# Power.net
KiCad netlist of a schematic drawn in Altium Designer
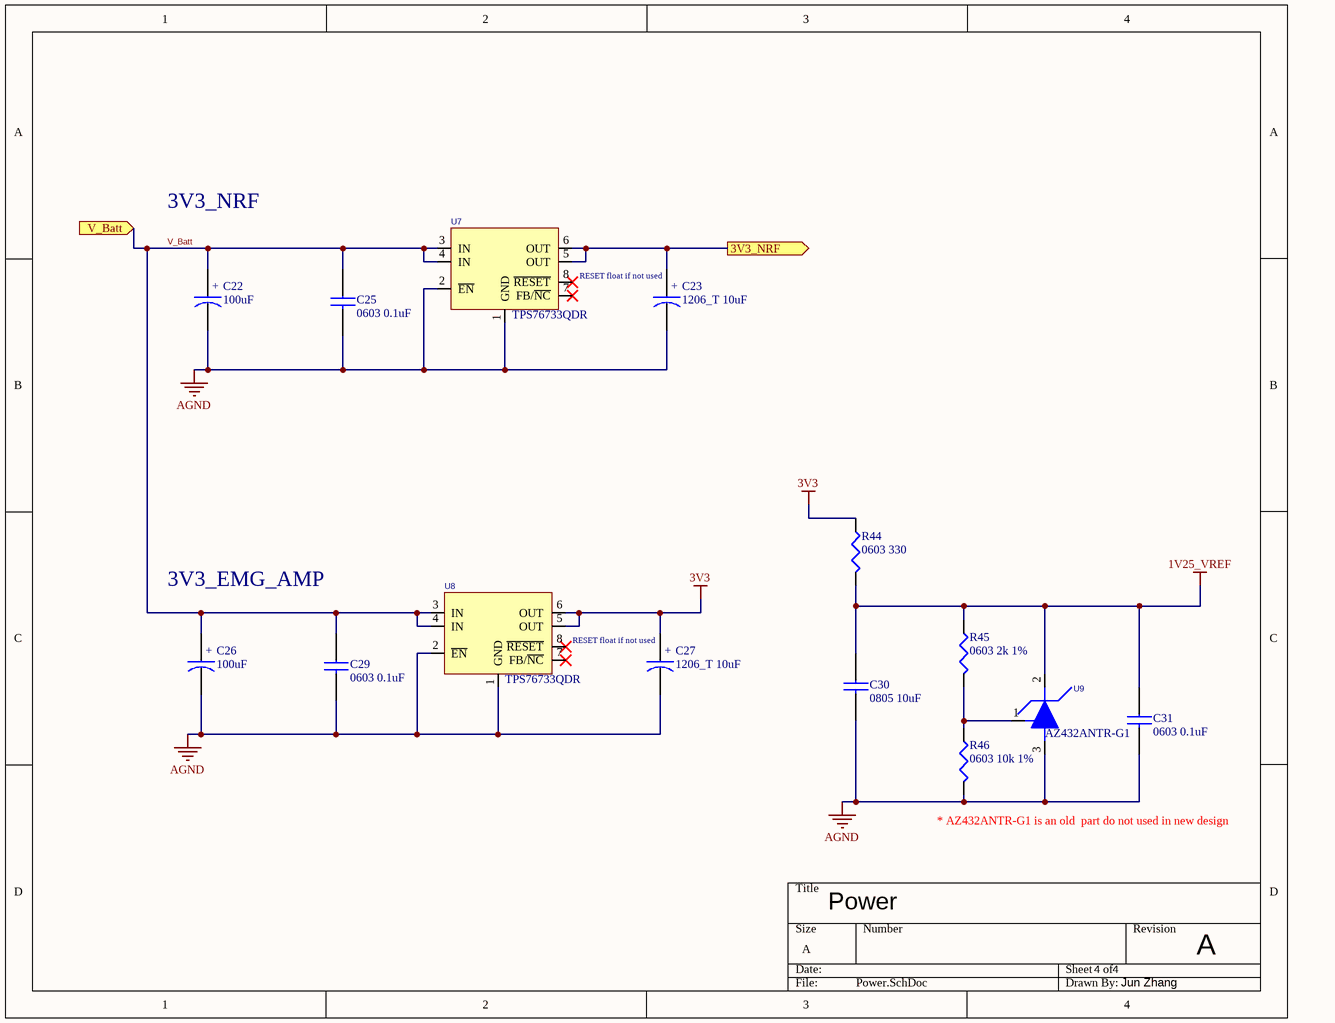
[diagram p0: Power.SchDoc]

(export (version "E")
  (design (tool "Eeschema 10.0.6"))
  (components
    (comp (ref "C22")
      (value "100uF")
      (footprint "CAPAE7866X61M")
      (description "Electrolytic 100uF")
      (fields
        (field (name "MANUFACTURER PART NUMBER") "AFK107M16D16T-F")
        (field (name "MANUFACTURER") "Cornell Dubilier Electronics (CDE)")
      )
      (libsource (lib "BioSens") (part "CAP_POL"))
    )
    (comp (ref "C23")
      (value "1206_T 10uF")
      (footprint "CAP_1206_TANT")
      (description "Tantalum CAP\r\nESR: 900mOhm\r\nRated: 10V")
      (fields
        (field (name "MANUFACTURER PART NUMBER") "TPSA106K010R0900")
        (field (name "MANUFACTURER") "KYOCERA AVX")
      )
      (libsource (lib "BioSens") (part "CAP_POL"))
    )
    (comp (ref "C25")
      (value "0603 0.1uF")
      (footprint "CAP_0603_CER")
      (description "Generic Cap for NC (No Polar)\r\nESR <30mOhm\r\nESL <1.5nH,\r\nX7R")
      (fields
        (field (name "MANUFACTURER") "KYOCERA AVX")
        (field (name "MANUFACTURER PART NUMBER") "06033C104K4T4A")
      )
      (libsource (lib "BioSens") (part "CAP_NP"))
    )
    (comp (ref "C26")
      (value "100uF")
      (footprint "CAPAE7866X61M")
      (description "Electrolytic 100uF")
      (fields
        (field (name "MANUFACTURER PART NUMBER") "AFK107M16D16T-F")
        (field (name "MANUFACTURER") "Cornell Dubilier Electronics (CDE)")
      )
      (libsource (lib "BioSens") (part "CAP_POL"))
    )
    (comp (ref "C27")
      (value "1206_T 10uF")
      (footprint "CAP_1206_TANT")
      (description "Tantalum CAP\r\nESR: 900mOhm\r\nRated: 10V")
      (fields
        (field (name "MANUFACTURER PART NUMBER") "TPSA106K010R0900")
        (field (name "MANUFACTURER") "KYOCERA AVX")
      )
      (libsource (lib "BioSens") (part "CAP_POL"))
    )
    (comp (ref "C29")
      (value "0603 0.1uF")
      (footprint "CAP_0603_CER")
      (description "Generic Cap for NC (No Polar)\r\nESR <30mOhm\r\nESL <1.5nH,\r\nX7R")
      (fields
        (field (name "MANUFACTURER") "KYOCERA AVX")
        (field (name "MANUFACTURER PART NUMBER") "06033C104K4T4A")
      )
      (libsource (lib "BioSens") (part "CAP_NP"))
    )
    (comp (ref "C30")
      (value "0805 10uF")
      (footprint "CAP_0805_CER")
      (description "Generic Cap for NC (No Polar)\r\nESR <30mOhm\r\nESL <1.5nH,\r\nX7R")
      (fields
        (field (name "MANUFACTURER") "KEMET")
        (field (name "MANUFACTURER PART NUMBER") "C0805C106M8RACTU")
      )
      (libsource (lib "BioSens") (part "CAP_NP"))
    )
    (comp (ref "C31")
      (value "0603 0.1uF")
      (footprint "CAP_0603_CER")
      (description "Generic Cap for NC (No Polar)\r\nESR <30mOhm\r\nESL <1.5nH,\r\nX7R")
      (fields
        (field (name "MANUFACTURER") "KEMET")
        (field (name "MANUFACTURER PART NUMBER") "C0603C104K5RAC7867")
      )
      (libsource (lib "BioSens") (part "CAP_NP"))
    )
    (comp (ref "R44")
      (value "0603 330")
      (footprint "0603")
      (description "Generic Resistor")
      (libsource (lib "BioSens") (part "RESISTOR"))
    )
    (comp (ref "R45")
      (value "0603 2k 1%")
      (footprint "0603")
      (description "Generic Resistor")
      (fields (field (name "MANUFACTURER") "YAGEO"))
      (libsource (lib "BioSens") (part "RESISTOR"))
    )
    (comp (ref "R46")
      (value "0603 10k 1%")
      (footprint "0603")
      (description "Generic Resistor")
      (fields (field (name "MANUFACTURER") "YAGEO"))
      (libsource (lib "BioSens") (part "RESISTOR"))
    )
    (comp (ref "U7")
      (value "TPS76733QDR")
      (footprint "SOIC127P600X175-8N")
      (description "IC REG LDO 3.3V 1A 8SOIC / LDO Regulator Pos 3.3V 1A 8-Pin SOIC T/R")
      (fields (field (name "MANUFACTURER") "Texas Instruments"))
      (libsource (lib "BioSens") (part "TPS76733QDR"))
    )
    (comp (ref "U8")
      (value "TPS76733QDR")
      (footprint "SOIC127P600X175-8N")
      (description "IC REG LDO 3.3V 1A 8SOIC / LDO Regulator Pos 3.3V 1A 8-Pin SOIC T/R")
      (fields (field (name "MANUFACTURER") "Texas Instruments"))
      (libsource (lib "BioSens") (part "TPS76733QDR"))
    )
    (comp (ref "U9")
      (value "AZ432ANTR-G1")
      (footprint "SOT95P245X110-3N")
      (description "V-Ref Adjustable/Precision/Programmable 1.25V to 18V 100mA 3-Pin SOT-23 T/R")
      (fields (field (name "MANUFACTURER") "Diodes") (field (name "TOLERANCE") "0.5%"))
      (libsource (lib "BioSens") (part "AZ432ANTR-G1"))
    )
  )
  (nets
    (net (code "1") (name "/3V3_NRF") (class "Default")
      (node (ref "C23") (pin "1") (pinfunction "1_1") (pintype "passive"))
      (node (ref "U7") (pin "5") (pinfunction "OUT_5") (pintype "passive"))
      (node (ref "U7") (pin "6") (pinfunction "OUT_6") (pintype "passive"))
    )
    (net (code "2") (name "/V_Batt") (class "Default")
      (node (ref "C22") (pin "1") (pinfunction "1_1") (pintype "passive"))
      (node (ref "C25") (pin "1") (pinfunction "1_1") (pintype "passive"))
      (node (ref "C26") (pin "1") (pinfunction "1_1") (pintype "passive"))
      (node (ref "C29") (pin "1") (pinfunction "1_1") (pintype "passive"))
      (node (ref "U7") (pin "3") (pinfunction "IN_3") (pintype "passive"))
      (node (ref "U7") (pin "4") (pinfunction "IN_4") (pintype "passive"))
      (node (ref "U8") (pin "3") (pinfunction "IN_3") (pintype "passive"))
      (node (ref "U8") (pin "4") (pinfunction "IN_4") (pintype "passive"))
    )
    (net (code "3") (name "1V25_VREF") (class "Default")
      (node (ref "C30") (pin "1") (pinfunction "1_1") (pintype "passive"))
      (node (ref "C31") (pin "1") (pinfunction "1_1") (pintype "passive"))
      (node (ref "R44") (pin "2") (pinfunction "2_2") (pintype "passive"))
      (node (ref "R45") (pin "1") (pinfunction "1_1") (pintype "passive"))
      (node (ref "U9") (pin "2") (pinfunction "Cathode_2") (pintype "passive"))
    )
    (net (code "4") (name "3V3") (class "Default")
      (node (ref "C27") (pin "1") (pinfunction "1_1") (pintype "passive"))
      (node (ref "R44") (pin "1") (pinfunction "1_1") (pintype "passive"))
      (node (ref "U8") (pin "5") (pinfunction "OUT_5") (pintype "passive"))
      (node (ref "U8") (pin "6") (pinfunction "OUT_6") (pintype "passive"))
    )
    (net (code "5") (name "AGND") (class "Default")
      (node (ref "C22") (pin "2") (pinfunction "2_2") (pintype "passive"))
      (node (ref "C23") (pin "2") (pinfunction "2_2") (pintype "passive"))
      (node (ref "C25") (pin "2") (pinfunction "2_2") (pintype "passive"))
      (node (ref "C26") (pin "2") (pinfunction "2_2") (pintype "passive"))
      (node (ref "C27") (pin "2") (pinfunction "2_2") (pintype "passive"))
      (node (ref "C29") (pin "2") (pinfunction "2_2") (pintype "passive"))
      (node (ref "C30") (pin "2") (pinfunction "2_2") (pintype "passive"))
      (node (ref "C31") (pin "2") (pinfunction "2_2") (pintype "passive"))
      (node (ref "R46") (pin "2") (pinfunction "2_2") (pintype "passive"))
      (node (ref "U7") (pin "1") (pinfunction "GND_1") (pintype "passive"))
      (node (ref "U7") (pin "2") (pinfunction "~{EN}_2") (pintype "passive"))
      (node (ref "U8") (pin "1") (pinfunction "GND_1") (pintype "passive"))
      (node (ref "U8") (pin "2") (pinfunction "~{EN}_2") (pintype "passive"))
      (node (ref "U9") (pin "3") (pinfunction "Anode_3") (pintype "passive"))
    )
    (net (code "6") (name "Net-(U9-REF)") (class "Default")
      (node (ref "R45") (pin "2") (pinfunction "2_2") (pintype "passive"))
      (node (ref "R46") (pin "1") (pinfunction "1_1") (pintype "passive"))
      (node (ref "U9") (pin "1") (pinfunction "REF_1") (pintype "passive"))
    )
    (net (code "7") (name "unconnected-(U7-FB{slash}~{NC}-Pad7)") (class "Default")
      (node (ref "U7") (pin "7") (pinfunction "FB/~{NC}_7") (pintype "passive+no_connect"))
    )
    (net (code "8") (name "unconnected-(U7-RESET-Pad8)") (class "Default")
      (node (ref "U7") (pin "8") (pinfunction "RESET_8") (pintype "passive+no_connect"))
    )
    (net (code "9") (name "unconnected-(U8-FB{slash}~{NC}-Pad7)") (class "Default")
      (node (ref "U8") (pin "7") (pinfunction "FB/~{NC}_7") (pintype "passive+no_connect"))
    )
    (net (code "10") (name "unconnected-(U8-RESET-Pad8)") (class "Default")
      (node (ref "U8") (pin "8") (pinfunction "RESET_8") (pintype "passive+no_connect"))
    )
  )
)
